# 5V-to-3_3V_Voltage__Regulator.net
KiCad netlist of a schematic drawn in Altium Designer
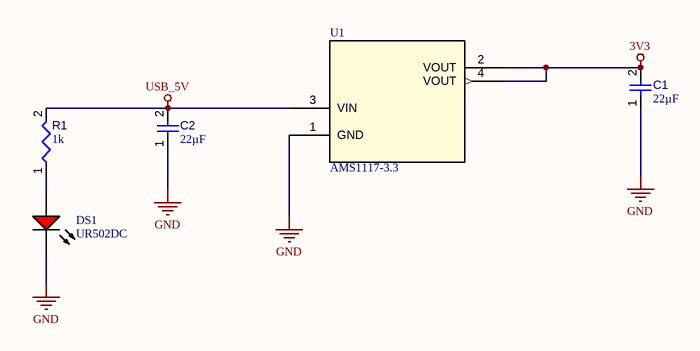
[diagram p0: 5V-to-3.3V_Voltage _Regulator.SchDoc]

(export (version "E")
  (design (tool "Eeschema 10.0.6"))
  (components
    (comp (ref "C1")
      (value "22µF")
      (footprint "CAPC0805(2012)145_L")
      (description "Chip Capacitor, 22µF +/-40%, 16V, 0805, Thickness 1.45 mm")
      (fields (field (name "TOLERANCE") "5%") (field (name "Comment") "Capacitor 22µF +/-40% 16V 0805"))
      (libsource (lib "Kylian Siemou Diemou Tchoya") (part "CAP-NP-2"))
    )
    (comp (ref "C2")
      (value "22µF")
      (footprint "CAPC0805(2012)145_L")
      (description "Chip Capacitor, 22µF +/-40%, 16V, 0805, Thickness 1.45 mm")
      (fields (field (name "TOLERANCE") "5%") (field (name "Comment") "Capacitor 22µF +/-40% 16V 0805"))
      (libsource (lib "Kylian Siemou Diemou Tchoya") (part "CAP-NP-2"))
    )
    (comp (ref "DS1")
      (value "UR502DC")
      (footprint "CGX-UR502DC")
      (description "Red LED, 80 mW, 30 mA, -25 to 85 degC, 2-Pin THD")
      (fields (field (name "POWER") "80mW") (field (name "MANUFACTURER") "Shenzhen CGX"))
      (libsource (lib "Kylian Siemou Diemou Tchoya") (part "LED-RED-AK-2"))
    )
    (comp (ref "R1")
      (value "1k")
      (footprint "RESC0805(2012)_L")
      (description "Chip Resistor, 1 kOhms, +/-5%, 125 mW, -55 to 155 degC, 0805")
      (fields (field (name "TOLERANCE") "5%") (field (name "POWER") "125mW"))
      (libsource (lib "Kylian Siemou Diemou Tchoya") (part "RES-2"))
    )
    (comp (ref "U1")
      (value "AMS1117-3.3")
      (footprint "SOT-223_UMW")
      (description "Description")
      (fields (field (name "COPYRIGHT") "Copyright (C) 2026 Ultra Librarian. All rights reserved."))
      (libsource (lib "AMS1117-3P3") (part "AMS1117-3.3"))
    )
  )
  (nets
    (net (code "1") (name "3V3") (class "Default")
      (node (ref "C1") (pin "2") (pinfunction "2_2") (pintype "passive"))
      (node (ref "U1") (pin "2") (pinfunction "VOUT_2") (pintype "power_in"))
      (node (ref "U1") (pin "4") (pinfunction "VOUT_4") (pintype "output"))
    )
    (net (code "2") (name "GND") (class "Default")
      (node (ref "C1") (pin "1") (pinfunction "1_1") (pintype "passive"))
      (node (ref "C2") (pin "1") (pinfunction "1_1") (pintype "passive"))
      (node (ref "DS1") (pin "2") (pinfunction "K_2") (pintype "passive"))
      (node (ref "U1") (pin "1") (pinfunction "GND_1") (pintype "power_in"))
    )
    (net (code "3") (name "Net-(DS1-A)") (class "Default")
      (node (ref "DS1") (pin "1") (pinfunction "A_1") (pintype "passive"))
      (node (ref "R1") (pin "1") (pinfunction "1_1") (pintype "passive"))
    )
    (net (code "4") (name "USB_5V") (class "Default")
      (node (ref "C2") (pin "2") (pinfunction "2_2") (pintype "passive"))
      (node (ref "R1") (pin "2") (pinfunction "2_2") (pintype "passive"))
      (node (ref "U1") (pin "3") (pinfunction "VIN_3") (pintype "power_in"))
    )
  )
)
